# Gremar_FController.net
KiCad netlist of a schematic drawn in Altium Designer
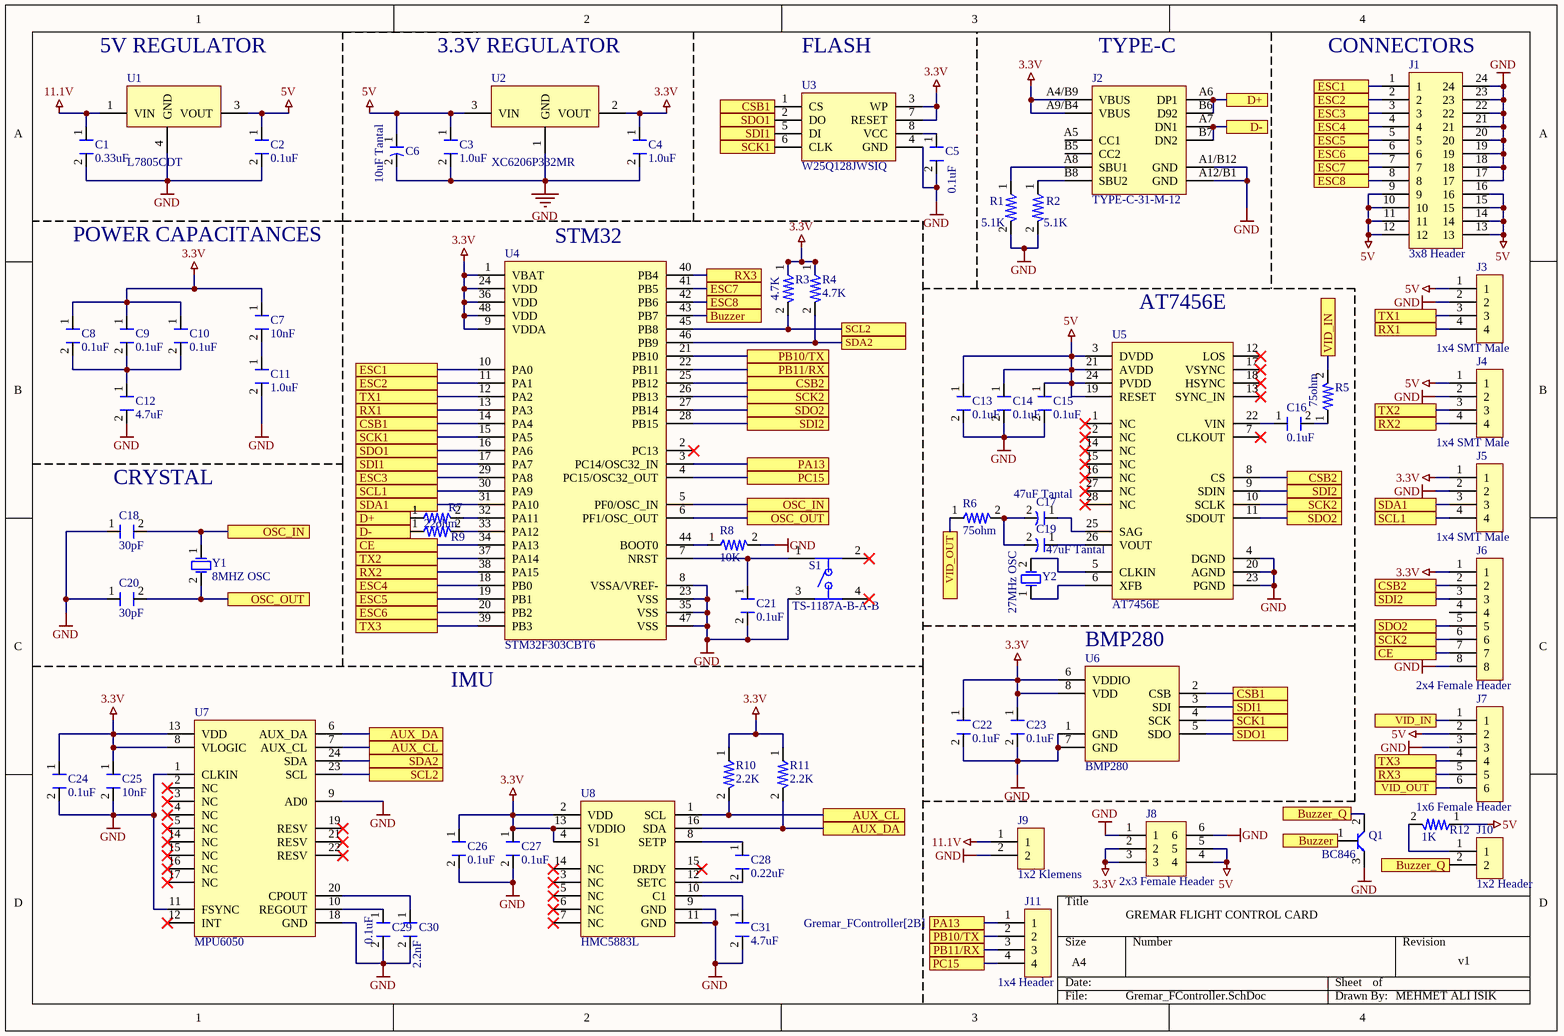
[diagram p0: Gremar_FController.SchDoc]

(export (version "E")
  (design (tool "Eeschema 10.0.6"))
  (components
    (comp (ref "C1")
      (value "0.33uF")
      (footprint "CAP - 0603")
      (description "0603 0.33uF Capacitor")
      (libsource (lib "Flight_Controller") (part "0.33uF"))
    )
    (comp (ref "C2")
      (value "0.1uF")
      (footprint "CAP - 0603")
      (description "0603 0.1uF Capacitor")
      (libsource (lib "Flight_Controller") (part "0.1uF"))
    )
    (comp (ref "C3")
      (value "1.0uF")
      (footprint "CAP - 0603")
      (description "0603 1.0uF Capacitor")
      (libsource (lib "Flight_Controller") (part "1.0uF"))
    )
    (comp (ref "C4")
      (value "1.0uF")
      (footprint "CAP - 0603")
      (description "0603 1.0uF Capacitor")
      (libsource (lib "Flight_Controller") (part "1.0uF"))
    )
    (comp (ref "C5")
      (value "0.1uF")
      (footprint "CAP - 0603")
      (description "0603 0.1uF Capacitor")
      (libsource (lib "Flight_Controller") (part "0.1uF"))
    )
    (comp (ref "C6")
      (value "10uF Tantal")
      (footprint "10uF Tantal")
      (description "10uF 16V 3Ω@100kHz -55℃~+125℃ ±10% CASE-A_3216 Tantalum Capacitors ROHS")
      (libsource (lib "Flight_Controller") (part "10uF Tantal"))
    )
    (comp (ref "C7")
      (value "10nF")
      (footprint "CAP - 0603")
      (description "0603 10nF Capacitor")
      (libsource (lib "Flight_Controller") (part "10nF"))
    )
    (comp (ref "C8")
      (value "0.1uF")
      (footprint "CAP - 0603")
      (description "0603 0.1uF Capacitor")
      (libsource (lib "Flight_Controller") (part "0.1uF"))
    )
    (comp (ref "C9")
      (value "0.1uF")
      (footprint "CAP - 0603")
      (description "0603 0.1uF Capacitor")
      (libsource (lib "Flight_Controller") (part "0.1uF"))
    )
    (comp (ref "C10")
      (value "0.1uF")
      (footprint "CAP - 0603")
      (description "0603 0.1uF Capacitor")
      (libsource (lib "Flight_Controller") (part "0.1uF"))
    )
    (comp (ref "C11")
      (value "1.0uF")
      (footprint "CAP - 0603")
      (description "0603 1.0uF Capacitor")
      (libsource (lib "Flight_Controller") (part "1.0uF"))
    )
    (comp (ref "C12")
      (value "4.7uF")
      (footprint "CAP - 0603")
      (description "0603 4.7uF Capacitor")
      (libsource (lib "Flight_Controller") (part "4.7uF"))
    )
    (comp (ref "C13")
      (value "0.1uF")
      (footprint "CAP - 0603")
      (description "0603 0.1uF Capacitor")
      (libsource (lib "Flight_Controller") (part "0.1uF"))
    )
    (comp (ref "C14")
      (value "0.1uF")
      (footprint "CAP - 0603")
      (description "0603 0.1uF Capacitor")
      (libsource (lib "Flight_Controller") (part "0.1uF"))
    )
    (comp (ref "C15")
      (value "0.1uF")
      (footprint "CAP - 0603")
      (description "0603 0.1uF Capacitor")
      (libsource (lib "Flight_Controller") (part "0.1uF"))
    )
    (comp (ref "C16")
      (value "0.1uF")
      (footprint "CAP - 0603")
      (description "0603 0.1uF Capacitor")
      (libsource (lib "Flight_Controller") (part "0.1uF"))
    )
    (comp (ref "C17")
      (value "47uF Tantal")
      (footprint "10uF Tantal")
      (description "0603 47uF Capacitor")
      (libsource (lib "Flight_Controller") (part "47uF Tantal"))
    )
    (comp (ref "C18")
      (value "30pF")
      (footprint "CAP - 0603")
      (description "0603 30pF Capacitor")
      (libsource (lib "Flight_Controller") (part "30pF"))
    )
    (comp (ref "C19")
      (value "47uF Tantal")
      (footprint "10uF Tantal")
      (description "0603 47uF Capacitor")
      (libsource (lib "Flight_Controller") (part "47uF Tantal"))
    )
    (comp (ref "C20")
      (value "30pF")
      (footprint "CAP - 0603")
      (description "0603 30pF Capacitor")
      (libsource (lib "Flight_Controller") (part "30pF"))
    )
    (comp (ref "C21")
      (value "0.1uF")
      (footprint "CAP - 0603")
      (description "0603 0.1uF Capacitor")
      (libsource (lib "Flight_Controller") (part "0.1uF"))
    )
    (comp (ref "C22")
      (value "0.1uF")
      (footprint "CAP - 0603")
      (description "0603 0.1uF Capacitor")
      (libsource (lib "Flight_Controller") (part "0.1uF"))
    )
    (comp (ref "C23")
      (value "0.1uF")
      (footprint "CAP - 0603")
      (description "0603 0.1uF Capacitor")
      (libsource (lib "Flight_Controller") (part "0.1uF"))
    )
    (comp (ref "C24")
      (value "0.1uF")
      (footprint "CAP - 0603")
      (description "0603 0.1uF Capacitor")
      (libsource (lib "Flight_Controller") (part "0.1uF"))
    )
    (comp (ref "C25")
      (value "10nF")
      (footprint "CAP - 0603")
      (description "0603 10nF Capacitor")
      (libsource (lib "Flight_Controller") (part "10nF"))
    )
    (comp (ref "C26")
      (value "0.1uF")
      (footprint "CAP - 0603")
      (description "0603 0.1uF Capacitor")
      (libsource (lib "Flight_Controller") (part "0.1uF"))
    )
    (comp (ref "C27")
      (value "0.1uF")
      (footprint "CAP - 0603")
      (description "0603 0.1uF Capacitor")
      (libsource (lib "Flight_Controller") (part "0.1uF"))
    )
    (comp (ref "C28")
      (value "0.22uF")
      (footprint "CAP - 0603")
      (description "0603 0.22uF Capacitor")
      (libsource (lib "Flight_Controller") (part "0.22uF"))
    )
    (comp (ref "C29")
      (value "0.1uF")
      (footprint "CAP - 0603")
      (description "0603 0.1uF Capacitor")
      (libsource (lib "Flight_Controller") (part "0.1uF"))
    )
    (comp (ref "C30")
      (value "2.2nF")
      (footprint "CAP - 0603")
      (description "0603 2.2nF Capacitor")
      (libsource (lib "Flight_Controller") (part "2.2nF"))
    )
    (comp (ref "C31")
      (value "4.7uF")
      (footprint "CAP - 0603")
      (description "0603 4.7uF Capacitor")
      (libsource (lib "Flight_Controller") (part "4.7uF"))
    )
    (comp (ref "J1")
      (value "3x8 Header")
      (footprint "3x8 Header")
      (description "3x8 Headear 2.54mm")
      (libsource (lib "Flight_Controller") (part "3x8 Header"))
    )
    (comp (ref "J2")
      (value "TYPE-C-31-M-12")
      (footprint "TYPE-C-31-M-12")
      (description "250mA 1 16 Female Type-C SMD USB Connectors ROHS")
      (libsource (lib "Gremar_FController") (part "TYPE-C-31-M-12"))
    )
    (comp (ref "J3")
      (value "1x4 SMT Male")
      (footprint "1x4 SMT Header")
      (description "1x4 SMT male header")
      (libsource (lib "Flight_Controller") (part "1x4 SMT Male"))
    )
    (comp (ref "J4")
      (value "1x4 SMT Male")
      (footprint "1x4 SMT Header")
      (description "1x4 SMT male header")
      (libsource (lib "Flight_Controller") (part "1x4 SMT Male"))
    )
    (comp (ref "J5")
      (value "1x4 SMT Male")
      (footprint "1x4 SMT Header")
      (description "1x4 SMT male header")
      (libsource (lib "Flight_Controller") (part "1x4 SMT Male"))
    )
    (comp (ref "J6")
      (value "2x4 Female Header")
      (footprint "2x4 Female Header")
      (description "2x4 Female Header 2.54mm")
      (libsource (lib "Flight_Controller") (part "2x4 Female Header"))
    )
    (comp (ref "J7")
      (value "1x6 Female Header")
      (footprint "1x6 FEMALE HEADER")
      (description "1x6 Female header 2.54mm")
      (libsource (lib "Gremar_FController") (part "1x6 Female Header"))
    )
    (comp (ref "J8")
      (value "2x3 Female Header")
      (footprint "2x3 Male Header")
      (description "2x3 Female header 2.54mm")
      (libsource (lib "Flight_Controller") (part "2x3 Female Header"))
    )
    (comp (ref "J9")
      (value "1x2 Klemens")
      (footprint "1x2 Klemens")
      (libsource (lib "Gremar_FController") (part "1x2 Klemens"))
    )
    (comp (ref "J10")
      (value "1x2 Header")
      (footprint "1x2 Header")
      (description "1x2 Header 2.54mm")
      (libsource (lib "Gremar_FController") (part "1x2 Header"))
    )
    (comp (ref "J11")
      (value "1x4 Header")
      (footprint "1x4 Header")
      (description "1x4 Header 2.54mm")
      (libsource (lib "Gremar_FController") (part "1x4 Header"))
    )
    (comp (ref "Q1")
      (value "BC846")
      (footprint "BC846")
      (description "SOT-23 NPN Transistor")
      (libsource (lib "Flight_Controller") (part "BC846"))
    )
    (comp (ref "R1")
      (value "5.1K")
      (footprint "RES - 0603")
      (description "0603 5.1K Resistor")
      (libsource (lib "Flight_Controller") (part "5.1K"))
    )
    (comp (ref "R2")
      (value "5.1K")
      (footprint "RES - 0603")
      (description "0603 5.1K Resistor")
      (libsource (lib "Flight_Controller") (part "5.1K"))
    )
    (comp (ref "R3")
      (value "4.7K")
      (footprint "RES - 0603")
      (description "0603 4.7K Resistor")
      (libsource (lib "Flight_Controller") (part "4.7K"))
    )
    (comp (ref "R4")
      (value "4.7K")
      (footprint "RES - 0603")
      (description "0603 4.7K Resistor")
      (libsource (lib "Flight_Controller") (part "4.7K"))
    )
    (comp (ref "R5")
      (value "75ohm")
      (footprint "RES - 0603")
      (description "0603 75ohm Resistor")
      (libsource (lib "Flight_Controller") (part "75ohm"))
    )
    (comp (ref "R6")
      (value "75ohm")
      (footprint "RES - 0603")
      (description "0603 75ohm Resistor")
      (libsource (lib "Flight_Controller") (part "75ohm"))
    )
    (comp (ref "R7")
      (value "22ohm")
      (footprint "RES - 0603")
      (description "0603 22ohm Resistor")
      (libsource (lib "Flight_Controller") (part "22ohm"))
    )
    (comp (ref "R8")
      (value "10K")
      (footprint "RES - 0603")
      (description "0603 10K Resistor")
      (libsource (lib "Flight_Controller") (part "10K"))
    )
    (comp (ref "R9")
      (value "22ohm")
      (footprint "RES - 0603")
      (description "0603 22ohm Resistor")
      (libsource (lib "Flight_Controller") (part "22ohm"))
    )
    (comp (ref "R10")
      (value "2.2K")
      (footprint "RES - 0603")
      (description "0603 2.2K Resistor")
      (libsource (lib "Flight_Controller") (part "2.2K"))
    )
    (comp (ref "R11")
      (value "2.2K")
      (footprint "RES - 0603")
      (description "0603 2.2K Resistor")
      (libsource (lib "Flight_Controller") (part "2.2K"))
    )
    (comp (ref "R12")
      (value "1K")
      (footprint "RES - 0603")
      (description "0603 1K Resistor")
      (libsource (lib "Flight_Controller") (part "1K"))
    )
    (comp (ref "S1")
      (value "TS-1187A-B-A-B")
      (footprint "TS-1187A-B-A-B")
      (libsource (lib "Flight_Controller") (part "TS-1187A-B-A-B"))
    )
    (comp (ref "U1")
      (value "L7805CDT")
      (footprint "L7805CDT-TR")
      (libsource (lib "Gremar_FController") (part "L7805CDT"))
    )
    (comp (ref "U2")
      (value "XC6206P332MR")
      (footprint "XC6206P332MR")
      (description "200mA 680mV@(100mA) Fixed 3.3V~3.3V Positive 1 6V SOT-23-3L Linear Voltage Regulators (LDO) ROHS")
      (libsource (lib "Gremar_FController") (part "XC6206P332MR"))
    )
    (comp (ref "U3")
      (value "W25Q128JWSIQ")
      (footprint "W25Q128JWSIQ")
      (description "SOIC-8_208mil NOR FLASH ROHS")
      (libsource (lib "Gremar_FController") (part "W25Q128JWSIQ"))
    )
    (comp (ref "U4")
      (value "STM32F303CBT6")
      (footprint "STM32F303CBT6")
      (description "ARM® Cortex®-M4 72MHz FLASH 2V ~ 3.6V 32-Bit LQFP-48_7x7x05P ST Microelectronics ROHS")
      (libsource (lib "Gremar_FController") (part "STM32F303CBT6"))
    )
    (comp (ref "U5")
      (value "AT7456E")
      (footprint "AT7456E")
      (description "EEPROM, TSSOP-28 Microcontroller Units (MCUs/MPUs/SOCs) ROHS")
      (libsource (lib "Gremar_FController") (part "AT7456E"))
    )
    (comp (ref "U6")
      (value "BMP280")
      (footprint "BMP280")
      (description "LGA-8 Gas Sensors ROHS")
      (libsource (lib "Gremar_FController") (part "BMP280"))
    )
    (comp (ref "U7")
      (value "MPU6050")
      (footprint "MPU-6050")
      (description "QFN-24_4x4x05P Attitude Sensors ROHSs")
      (libsource (lib "Gremar_FController") (part "MPU6050"))
    )
    (comp (ref "U8")
      (value "HMC5883L")
      (footprint "HMC5883L")
      (description "LCC-16 Magnetic Sensors ROHS")
      (libsource (lib "Gremar_FController") (part "HMC5883L"))
    )
    (comp (ref "Y1")
      (value "8MHZ OSC")
      (footprint "8MHZ RESONATOR")
      (description "8MHz ±20ppm 20pF 80Ω SMD-5032_2P SMD Crystal Resonators RoHS")
      (libsource (lib "Gremar_FController") (part "8MHZ OSC"))
    )
    (comp (ref "Y2")
      (value "27MHz OSC")
      (footprint "27MHZ OSC - 7A27000010")
      (description "27MHz ±15ppm 20pF 50Ω SMD-5032_2P SMD Crystal Resonators RoHS")
      (libsource (lib "Gremar_FController") (part "27MHz OSC"))
    )
  )
  (nets
    (net (code "1") (name "/AUX_CL") (class "Default")
      (node (ref "R10") (pin "2") (pinfunction "2_2") (pintype "passive"))
      (node (ref "U7") (pin "7") (pinfunction "AUX_CL_7") (pintype "passive"))
      (node (ref "U8") (pin "1") (pinfunction "SCL_1") (pintype "passive"))
    )
    (net (code "2") (name "/AUX_DA") (class "Default")
      (node (ref "R11") (pin "2") (pinfunction "2_2") (pintype "passive"))
      (node (ref "U7") (pin "6") (pinfunction "AUX_DA_6") (pintype "passive"))
      (node (ref "U8") (pin "16") (pinfunction "SDA_16") (pintype "passive"))
    )
    (net (code "3") (name "/Buzzer") (class "Default")
      (node (ref "Q1") (pin "1") (pinfunction "1_1") (pintype "passive"))
      (node (ref "U4") (pin "43") (pinfunction "PB7_43") (pintype "passive"))
    )
    (net (code "4") (name "/Buzzer_Q") (class "Default")
      (node (ref "J10") (pin "2") (pinfunction "2_2") (pintype "passive"))
      (node (ref "Q1") (pin "2") (pinfunction "2_2") (pintype "passive"))
    )
    (net (code "5") (name "/CE") (class "Default")
      (node (ref "J6") (pin "7") (pinfunction "7_7") (pintype "passive"))
      (node (ref "U4") (pin "34") (pinfunction "PA13_34") (pintype "passive"))
    )
    (net (code "6") (name "/CSB1") (class "Default")
      (node (ref "U3") (pin "1") (pinfunction "CS_1") (pintype "passive"))
      (node (ref "U4") (pin "14") (pinfunction "PA4_14") (pintype "passive"))
      (node (ref "U6") (pin "2") (pinfunction "CSB_2") (pintype "passive"))
    )
    (net (code "7") (name "/CSB2") (class "Default")
      (node (ref "J6") (pin "2") (pinfunction "2_2") (pintype "passive"))
      (node (ref "U4") (pin "25") (pinfunction "PB12_25") (pintype "passive"))
      (node (ref "U5") (pin "8") (pinfunction "CS_8") (pintype "passive"))
    )
    (net (code "8") (name "/D+") (class "Default")
      (node (ref "J2") (pin "A6") (pinfunction "DP1_A6") (pintype "passive"))
      (node (ref "J2") (pin "B6") (pinfunction "D92_B6") (pintype "passive"))
      (node (ref "R7") (pin "1") (pinfunction "1_1") (pintype "passive"))
    )
    (net (code "9") (name "/D-") (class "Default")
      (node (ref "J2") (pin "A7") (pinfunction "DN1_A7") (pintype "passive"))
      (node (ref "J2") (pin "B7") (pinfunction "DN2_B7") (pintype "passive"))
      (node (ref "R9") (pin "1") (pinfunction "1_1") (pintype "passive"))
    )
    (net (code "10") (name "/ESC1") (class "Default")
      (node (ref "J1") (pin "1") (pinfunction "1_1") (pintype "passive"))
      (node (ref "U4") (pin "10") (pinfunction "PA0_10") (pintype "passive"))
    )
    (net (code "11") (name "/ESC2") (class "Default")
      (node (ref "J1") (pin "2") (pinfunction "2_2") (pintype "passive"))
      (node (ref "U4") (pin "11") (pinfunction "PA1_11") (pintype "passive"))
    )
    (net (code "12") (name "/ESC3") (class "Default")
      (node (ref "J1") (pin "3") (pinfunction "3_3") (pintype "passive"))
      (node (ref "U4") (pin "29") (pinfunction "PA8_29") (pintype "passive"))
    )
    (net (code "13") (name "/ESC4") (class "Default")
      (node (ref "J1") (pin "4") (pinfunction "4_4") (pintype "passive"))
      (node (ref "U4") (pin "18") (pinfunction "PB0_18") (pintype "passive"))
    )
    (net (code "14") (name "/ESC5") (class "Default")
      (node (ref "J1") (pin "5") (pinfunction "5_5") (pintype "passive"))
      (node (ref "U4") (pin "19") (pinfunction "PB1_19") (pintype "passive"))
    )
    (net (code "15") (name "/ESC6") (class "Default")
      (node (ref "J1") (pin "6") (pinfunction "6_6") (pintype "passive"))
      (node (ref "U4") (pin "20") (pinfunction "PB2_20") (pintype "passive"))
    )
    (net (code "16") (name "/ESC7") (class "Default")
      (node (ref "J1") (pin "7") (pinfunction "7_7") (pintype "passive"))
      (node (ref "U4") (pin "41") (pinfunction "PB5_41") (pintype "passive"))
    )
    (net (code "17") (name "/ESC8") (class "Default")
      (node (ref "J1") (pin "8") (pinfunction "8_8") (pintype "passive"))
      (node (ref "U4") (pin "42") (pinfunction "PB6_42") (pintype "passive"))
    )
    (net (code "18") (name "/OSC_IN") (class "Default")
      (node (ref "C18") (pin "2") (pinfunction "2_2") (pintype "passive"))
      (node (ref "U4") (pin "5") (pinfunction "PF0/OSC_IN_5") (pintype "passive"))
      (node (ref "Y1") (pin "1") (pinfunction "1_1") (pintype "passive"))
    )
    (net (code "19") (name "/OSC_OUT") (class "Default")
      (node (ref "C20") (pin "2") (pinfunction "2_2") (pintype "passive"))
      (node (ref "U4") (pin "6") (pinfunction "PF1/OSC_OUT_6") (pintype "passive"))
      (node (ref "Y1") (pin "2") (pinfunction "2_2") (pintype "passive"))
    )
    (net (code "20") (name "/PA13") (class "Default")
      (node (ref "J11") (pin "1") (pinfunction "1_1") (pintype "passive"))
      (node (ref "U4") (pin "3") (pinfunction "PC14/OSC32_IN_3") (pintype "passive"))
    )
    (net (code "21") (name "/PB10{slash}TX") (class "Default")
      (node (ref "J11") (pin "2") (pinfunction "2_2") (pintype "passive"))
      (node (ref "U4") (pin "21") (pinfunction "PB10_21") (pintype "passive"))
    )
    (net (code "22") (name "/PB11{slash}RX") (class "Default")
      (node (ref "J11") (pin "3") (pinfunction "3_3") (pintype "passive"))
      (node (ref "U4") (pin "22") (pinfunction "PB11_22") (pintype "passive"))
    )
    (net (code "23") (name "/PC15") (class "Default")
      (node (ref "J11") (pin "4") (pinfunction "4_4") (pintype "passive"))
      (node (ref "U4") (pin "4") (pinfunction "PC15/OSC32_OUT_4") (pintype "passive"))
    )
    (net (code "24") (name "/RX1") (class "Default")
      (node (ref "J3") (pin "4") (pinfunction "4_4") (pintype "passive"))
      (node (ref "U4") (pin "13") (pinfunction "PA3_13") (pintype "passive"))
    )
    (net (code "25") (name "/RX2") (class "Default")
      (node (ref "J4") (pin "4") (pinfunction "4_4") (pintype "passive"))
      (node (ref "U4") (pin "38") (pinfunction "PA15_38") (pintype "passive"))
    )
    (net (code "26") (name "/RX3") (class "Default")
      (node (ref "J7") (pin "5") (pinfunction "5_5") (pintype "passive"))
      (node (ref "U4") (pin "40") (pinfunction "PB4_40") (pintype "passive"))
    )
    (net (code "27") (name "/SCK1") (class "Default")
      (node (ref "U3") (pin "6") (pinfunction "CLK_6") (pintype "passive"))
      (node (ref "U4") (pin "15") (pinfunction "PA5_15") (pintype "passive"))
      (node (ref "U6") (pin "4") (pinfunction "SCK_4") (pintype "passive"))
    )
    (net (code "28") (name "/SCK2") (class "Default")
      (node (ref "J6") (pin "6") (pinfunction "6_6") (pintype "passive"))
      (node (ref "U4") (pin "26") (pinfunction "PB13_26") (pintype "passive"))
      (node (ref "U5") (pin "10") (pinfunction "SCLK_10") (pintype "passive"))
    )
    (net (code "29") (name "/SCL1") (class "Default")
      (node (ref "J5") (pin "4") (pinfunction "4_4") (pintype "passive"))
      (node (ref "U4") (pin "30") (pinfunction "PA9_30") (pintype "passive"))
    )
    (net (code "30") (name "/SCL2") (class "Default")
      (node (ref "R3") (pin "2") (pinfunction "2_2") (pintype "passive"))
      (node (ref "U4") (pin "45") (pinfunction "PB8_45") (pintype "passive"))
      (node (ref "U7") (pin "23") (pinfunction "SCL_23") (pintype "passive"))
    )
    (net (code "31") (name "/SDA1") (class "Default")
      (node (ref "J5") (pin "3") (pinfunction "3_3") (pintype "passive"))
      (node (ref "U4") (pin "31") (pinfunction "PA10_31") (pintype "passive"))
    )
    (net (code "32") (name "/SDA2") (class "Default")
      (node (ref "R4") (pin "2") (pinfunction "2_2") (pintype "passive"))
      (node (ref "U4") (pin "46") (pinfunction "PB9_46") (pintype "passive"))
      (node (ref "U7") (pin "24") (pinfunction "SDA_24") (pintype "passive"))
    )
    (net (code "33") (name "/SDI1") (class "Default")
      (node (ref "U3") (pin "5") (pinfunction "DI_5") (pintype "passive"))
      (node (ref "U4") (pin "17") (pinfunction "PA7_17") (pintype "passive"))
      (node (ref "U6") (pin "3") (pinfunction "SDI_3") (pintype "passive"))
    )
    (net (code "34") (name "/SDI2") (class "Default")
      (node (ref "J6") (pin "3") (pinfunction "3_3") (pintype "passive"))
      (node (ref "U4") (pin "28") (pinfunction "PB15_28") (pintype "passive"))
      (node (ref "U5") (pin "9") (pinfunction "SDIN_9") (pintype "passive"))
    )
    (net (code "35") (name "/SDO1") (class "Default")
      (node (ref "U3") (pin "2") (pinfunction "DO_2") (pintype "passive"))
      (node (ref "U4") (pin "16") (pinfunction "PA6_16") (pintype "passive"))
      (node (ref "U6") (pin "5") (pinfunction "SDO_5") (pintype "passive"))
    )
    (net (code "36") (name "/SDO2") (class "Default")
      (node (ref "J6") (pin "5") (pinfunction "5_5") (pintype "passive"))
      (node (ref "U4") (pin "27") (pinfunction "PB14_27") (pintype "passive"))
      (node (ref "U5") (pin "11") (pinfunction "SDOUT_11") (pintype "passive"))
    )
    (net (code "37") (name "/TX1") (class "Default")
      (node (ref "J3") (pin "3") (pinfunction "3_3") (pintype "passive"))
      (node (ref "U4") (pin "12") (pinfunction "PA2_12") (pintype "passive"))
    )
    (net (code "38") (name "/TX2") (class "Default")
      (node (ref "J4") (pin "3") (pinfunction "3_3") (pintype "passive"))
      (node (ref "U4") (pin "37") (pinfunction "PA14_37") (pintype "passive"))
    )
    (net (code "39") (name "/TX3") (class "Default")
      (node (ref "J7") (pin "4") (pinfunction "4_4") (pintype "passive"))
      (node (ref "U4") (pin "39") (pinfunction "PB3_39") (pintype "passive"))
    )
    (net (code "40") (name "/VID_IN") (class "Default")
      (node (ref "J7") (pin "1") (pinfunction "1_1") (pintype "passive"))
      (node (ref "R5") (pin "2") (pinfunction "2_2") (pintype "passive"))
    )
    (net (code "41") (name "/VID_OUT") (class "Default")
      (node (ref "J7") (pin "6") (pinfunction "6_6") (pintype "passive"))
      (node (ref "R6") (pin "1") (pinfunction "1_1") (pintype "passive"))
    )
    (net (code "42") (name "3.3V") (class "Default")
      (node (ref "C10") (pin "1") (pinfunction "1_1") (pintype "passive"))
      (node (ref "C22") (pin "1") (pinfunction "1_1") (pintype "passive"))
      (node (ref "C23") (pin "1") (pinfunction "1_1") (pintype "passive"))
      (node (ref "C24") (pin "1") (pinfunction "1_1") (pintype "passive"))
      (node (ref "C25") (pin "1") (pinfunction "1_1") (pintype "passive"))
      (node (ref "C26") (pin "1") (pinfunction "1_1") (pintype "passive"))
      (node (ref "C27") (pin "1") (pinfunction "1_1") (pintype "passive"))
      (node (ref "C4") (pin "1") (pinfunction "1_1") (pintype "passive"))
      (node (ref "C7") (pin "1") (pinfunction "1_1") (pintype "passive"))
      (node (ref "C8") (pin "1") (pinfunction "1_1") (pintype "passive"))
      (node (ref "C9") (pin "1") (pinfunction "1_1") (pintype "passive"))
      (node (ref "J2") (pin "A4/B9") (pinfunction "VBUS_A4/B9") (pintype "passive"))
      (node (ref "J2") (pin "A9/B4") (pinfunction "VBUS_A9/B4") (pintype "passive"))
      (node (ref "J5") (pin "1") (pinfunction "1_1") (pintype "passive"))
      (node (ref "J6") (pin "1") (pinfunction "1_1") (pintype "passive"))
      (node (ref "J8") (pin "2") (pinfunction "2_2") (pintype "passive"))
      (node (ref "J8") (pin "3") (pinfunction "3_3") (pintype "passive"))
      (node (ref "R10") (pin "1") (pinfunction "1_1") (pintype "passive"))
      (node (ref "R11") (pin "1") (pinfunction "1_1") (pintype "passive"))
      (node (ref "R3") (pin "1") (pinfunction "1_1") (pintype "passive"))
      (node (ref "R4") (pin "1") (pinfunction "1_1") (pintype "passive"))
      (node (ref "U2") (pin "2") (pinfunction "VOUT_2") (pintype "passive"))
      (node (ref "U3") (pin "3") (pinfunction "WP_3") (pintype "passive"))
      (node (ref "U3") (pin "7") (pinfunction "RESET_7") (pintype "passive"))
      (node (ref "U4") (pin "1") (pinfunction "VBAT_1") (pintype "passive"))
      (node (ref "U4") (pin "24") (pinfunction "VDD_24") (pintype "passive"))
      (node (ref "U4") (pin "36") (pinfunction "VDD_36") (pintype "passive"))
      (node (ref "U4") (pin "48") (pinfunction "VDD_48") (pintype "passive"))
      (node (ref "U4") (pin "9") (pinfunction "VDDA_9") (pintype "passive"))
      (node (ref "U6") (pin "6") (pinfunction "VDDIO_6") (pintype "passive"))
      (node (ref "U6") (pin "8") (pinfunction "VDD_8") (pintype "passive"))
      (node (ref "U7") (pin "13") (pinfunction "VDD_13") (pintype "passive"))
      (node (ref "U7") (pin "8") (pinfunction "VLOGIC_8") (pintype "passive"))
      (node (ref "U8") (pin "13") (pinfunction "VDDIO_13") (pintype "passive"))
      (node (ref "U8") (pin "2") (pinfunction "VDD_2") (pintype "passive"))
      (node (ref "U8") (pin "4") (pinfunction "S1_4") (pintype "passive"))
    )
    (net (code "43") (name "5V") (class "Default")
      (node (ref "C13") (pin "1") (pinfunction "1_1") (pintype "passive"))
      (node (ref "C14") (pin "1") (pinfunction "1_1") (pintype "passive"))
      (node (ref "C15") (pin "1") (pinfunction "1_1") (pintype "passive"))
      (node (ref "C2") (pin "1") (pinfunction "1_1") (pintype "passive"))
      (node (ref "C3") (pin "1") (pinfunction "1_1") (pintype "passive"))
      (node (ref "C6") (pin "1") (pinfunction "1_1") (pintype "passive"))
      (node (ref "J1") (pin "10") (pinfunction "10_10") (pintype "passive"))
      (node (ref "J1") (pin "11") (pinfunction "11_11") (pintype "passive"))
      (node (ref "J1") (pin "12") (pinfunction "12_12") (pintype "passive"))
      (node (ref "J1") (pin "13") (pinfunction "13_13") (pintype "passive"))
      (node (ref "J1") (pin "14") (pinfunction "14_14") (pintype "passive"))
      (node (ref "J1") (pin "15") (pinfunction "15_15") (pintype "passive"))
      (node (ref "J1") (pin "16") (pinfunction "16_16") (pintype "passive"))
      (node (ref "J1") (pin "9") (pinfunction "9_9") (pintype "passive"))
      (node (ref "J3") (pin "1") (pinfunction "1_1") (pintype "passive"))
      (node (ref "J4") (pin "1") (pinfunction "1_1") (pintype "passive"))
      (node (ref "J7") (pin "2") (pinfunction "2_2") (pintype "passive"))
      (node (ref "J8") (pin "4") (pinfunction "4_4") (pintype "passive"))
      (node (ref "J8") (pin "5") (pinfunction "5_5") (pintype "passive"))
      (node (ref "R12") (pin "1") (pinfunction "1_1") (pintype "passive"))
      (node (ref "U1") (pin "3") (pinfunction "VOUT_3") (pintype "passive"))
      (node (ref "U2") (pin "3") (pinfunction "VIN_3") (pintype "passive"))
      (node (ref "U5") (pin "19") (pinfunction "RESET_19") (pintype "passive"))
      (node (ref "U5") (pin "21") (pinfunction "AVDD_21") (pintype "passive"))
      (node (ref "U5") (pin "24") (pinfunction "PVDD_24") (pintype "passive"))
      (node (ref "U5") (pin "3") (pinfunction "DVDD_3") (pintype "passive"))
    )
    (net (code "44") (name "11.1V") (class "Default")
      (node (ref "C1") (pin "1") (pinfunction "1_1") (pintype "passive"))
      (node (ref "J9") (pin "1") (pinfunction "1_1") (pintype "passive"))
      (node (ref "U1") (pin "1") (pinfunction "VIN_1") (pintype "passive"))
    )
    (net (code "45") (name "GND") (class "Default")
      (node (ref "C1") (pin "2") (pinfunction "2_2") (pintype "passive"))
      (node (ref "C11") (pin "2") (pinfunction "2_2") (pintype "passive"))
      (node (ref "C12") (pin "2") (pinfunction "2_2") (pintype "passive"))
      (node (ref "C13") (pin "2") (pinfunction "2_2") (pintype "passive"))
      (node (ref "C14") (pin "2") (pinfunction "2_2") (pintype "passive"))
      (node (ref "C15") (pin "2") (pinfunction "2_2") (pintype "passive"))
      (node (ref "C18") (pin "1") (pinfunction "1_1") (pintype "passive"))
      (node (ref "C2") (pin "2") (pinfunction "2_2") (pintype "passive"))
      (node (ref "C20") (pin "1") (pinfunction "1_1") (pintype "passive"))
      (node (ref "C21") (pin "2") (pinfunction "2_2") (pintype "passive"))
      (node (ref "C22") (pin "2") (pinfunction "2_2") (pintype "passive"))
      (node (ref "C23") (pin "2") (pinfunction "2_2") (pintype "passive"))
      (node (ref "C24") (pin "2") (pinfunction "2_2") (pintype "passive"))
      (node (ref "C25") (pin "2") (pinfunction "2_2") (pintype "passive"))
      (node (ref "C26") (pin "2") (pinfunction "2_2") (pintype "passive"))
      (node (ref "C27") (pin "2") (pinfunction "2_2") (pintype "passive"))
      (node (ref "C29") (pin "2") (pinfunction "2_2") (pintype "passive"))
      (node (ref "C3") (pin "2") (pinfunction "2_2") (pintype "passive"))
      (node (ref "C30") (pin "2") (pinfunction "2_2") (pintype "passive"))
      (node (ref "C31") (pin "2") (pinfunction "2_2") (pintype "passive"))
      (node (ref "C4") (pin "2") (pinfunction "2_2") (pintype "passive"))
      (node (ref "C5") (pin "2") (pinfunction "2_2") (pintype "passive"))
      (node (ref "C6") (pin "2") (pinfunction "2_2") (pintype "passive"))
      (node (ref "J1") (pin "17") (pinfunction "17_17") (pintype "passive"))
      (node (ref "J1") (pin "18") (pinfunction "18_18") (pintype "passive"))
      (node (ref "J1") (pin "19") (pinfunction "19_19") (pintype "passive"))
      (node (ref "J1") (pin "20") (pinfunction "20_20") (pintype "passive"))
      (node (ref "J1") (pin "21") (pinfunction "21_21") (pintype "passive"))
      (node (ref "J1") (pin "22") (pinfunction "22_22") (pintype "passive"))
      (node (ref "J1") (pin "23") (pinfunction "23_23") (pintype "passive"))
      (node (ref "J1") (pin "24") (pinfunction "24_24") (pintype "passive"))
      (node (ref "J2") (pin "A1/B12") (pinfunction "GND_A1/B12") (pintype "passive"))
      (node (ref "J2") (pin "A12/B1") (pinfunction "GND_A12/B1") (pintype "passive"))
      (node (ref "J3") (pin "2") (pinfunction "2_2") (pintype "passive"))
      (node (ref "J4") (pin "2") (pinfunction "2_2") (pintype "passive"))
      (node (ref "J5") (pin "2") (pinfunction "2_2") (pintype "passive"))
      (node (ref "J6") (pin "8") (pinfunction "8_8") (pintype "passive"))
      (node (ref "J7") (pin "3") (pinfunction "3_3") (pintype "passive"))
      (node (ref "J8") (pin "1") (pinfunction "1_1") (pintype "passive"))
      (node (ref "J8") (pin "6") (pinfunction "6_6") (pintype "passive"))
      (node (ref "J9") (pin "2") (pinfunction "2_2") (pintype "passive"))
      (node (ref "Q1") (pin "3") (pinfunction "3_3") (pintype "passive"))
      (node (ref "R1") (pin "2") (pinfunction "2_2") (pintype "passive"))
      (node (ref "R2") (pin "2") (pinfunction "2_2") (pintype "passive"))
      (node (ref "R8") (pin "2") (pinfunction "2_2") (pintype "passive"))
      (node (ref "S1") (pin "3") (pinfunction "3_3") (pintype "passive"))
      (node (ref "U1") (pin "4") (pinfunction "GND_4") (pintype "passive"))
      (node (ref "U2") (pin "1") (pinfunction "GND_1") (pintype "passive"))
      (node (ref "U3") (pin "4") (pinfunction "GND_4") (pintype "passive"))
      (node (ref "U4") (pin "23") (pinfunction "VSS_23") (pintype "passive"))
      (node (ref "U4") (pin "35") (pinfunction "VSS_35") (pintype "passive"))
      (node (ref "U4") (pin "47") (pinfunction "VSS_47") (pintype "passive"))
      (node (ref "U4") (pin "8") (pinfunction "VSSA/VREF-_8") (pintype "passive"))
      (node (ref "U5") (pin "20") (pinfunction "AGND_20") (pintype "passive"))
      (node (ref "U5") (pin "23") (pinfunction "PGND_23") (pintype "passive"))
      (node (ref "U5") (pin "4") (pinfunction "DGND_4") (pintype "passive"))
      (node (ref "U6") (pin "1") (pinfunction "GND_1") (pintype "passive"))
      (node (ref "U6") (pin "7") (pinfunction "GND_7") (pintype "passive"))
      (node (ref "U7") (pin "1") (pinfunction "CLKIN_1") (pintype "passive"))
      (node (ref "U7") (pin "11") (pinfunction "FSYNC_11") (pintype "passive"))
      (node (ref "U7") (pin "18") (pinfunction "GND_18") (pintype "passive"))
      (node (ref "U7") (pin "9") (pinfunction "AD0_9") (pintype "passive"))
      (node (ref "U8") (pin "11") (pinfunction "GND_11") (pintype "passive"))
      (node (ref "U8") (pin "9") (pinfunction "GND_9") (pintype "passive"))
    )
    (net (code "46") (name "Net-(C10-Pad2)") (class "Default")
      (node (ref "C10") (pin "2") (pinfunction "2_2") (pintype "passive"))
      (node (ref "C12") (pin "1") (pinfunction "1_1") (pintype "passive"))
      (node (ref "C8") (pin "2") (pinfunction "2_2") (pintype "passive"))
      (node (ref "C9") (pin "2") (pinfunction "2_2") (pintype "passive"))
    )
    (net (code "47") (name "Net-(C11-Pad1)") (class "Default")
      (node (ref "C11") (pin "1") (pinfunction "1_1") (pintype "passive"))
      (node (ref "C7") (pin "2") (pinfunction "2_2") (pintype "passive"))
    )
    (net (code "48") (name "Net-(C16-Pad2)") (class "Default")
      (node (ref "C16") (pin "2") (pinfunction "2_2") (pintype "passive"))
      (node (ref "R5") (pin "1") (pinfunction "1_1") (pintype "passive"))
    )
    (net (code "49") (name "Net-(C17-Pad2)") (class "Default")
      (node (ref "C17") (pin "2") (pinfunction "2_2") (pintype "passive"))
      (node (ref "C19") (pin "2") (pinfunction "2_2") (pintype "passive"))
      (node (ref "R6") (pin "2") (pinfunction "2_2") (pintype "passive"))
    )
    (net (code "50") (name "Net-(J2-SBU1)") (class "Default")
      (node (ref "J2") (pin "A8") (pinfunction "SBU1_A8") (pintype "passive"))
      (node (ref "R1") (pin "1") (pinfunction "1_1") (pintype "passive"))
    )
    (net (code "51") (name "Net-(J2-SBU2)") (class "Default")
      (node (ref "J2") (pin "B8") (pinfunction "SBU2_B8") (pintype "passive"))
      (node (ref "R2") (pin "1") (pinfunction "1_1") (pintype "passive"))
    )
    (net (code "52") (name "Net-(J10-Pad1)") (class "Default")
      (node (ref "J10") (pin "1") (pinfunction "1_1") (pintype "passive"))
      (node (ref "R12") (pin "2") (pinfunction "2_2") (pintype "passive"))
    )
    (net (code "53") (name "Net-(U3-VCC)") (class "Default")
      (node (ref "C5") (pin "1") (pinfunction "1_1") (pintype "passive"))
      (node (ref "U3") (pin "8") (pinfunction "VCC_8") (pintype "passive"))
    )
    (net (code "54") (name "Net-(U4-BOOT0)") (class "Default")
      (node (ref "R8") (pin "1") (pinfunction "1_1") (pintype "passive"))
      (node (ref "U4") (pin "44") (pinfunction "BOOT0_44") (pintype "passive"))
    )
    (net (code "55") (name "Net-(U4-NRST)") (class "Default")
      (node (ref "C21") (pin "1") (pinfunction "1_1") (pintype "passive"))
      (node (ref "S1") (pin "1") (pinfunction "1_1") (pintype "passive"))
      (node (ref "U4") (pin "7") (pinfunction "NRST_7") (pintype "passive"))
    )
    (net (code "56") (name "Net-(U4-PA11)") (class "Default")
      (node (ref "R7") (pin "2") (pinfunction "2_2") (pintype "passive"))
      (node (ref "U4") (pin "32") (pinfunction "PA11_32") (pintype "passive"))
    )
    (net (code "57") (name "Net-(U4-PA12)") (class "Default")
      (node (ref "R9") (pin "2") (pinfunction "2_2") (pintype "passive"))
      (node (ref "U4") (pin "33") (pinfunction "PA12_33") (pintype "passive"))
    )
    (net (code "58") (name "Net-(U5-CLKIN)") (class "Default")
      (node (ref "U5") (pin "5") (pinfunction "CLKIN_5") (pintype "passive"))
      (node (ref "Y2") (pin "2") (pinfunction "2_2") (pintype "passive"))
    )
    (net (code "59") (name "Net-(U5-SAG)") (class "Default")
      (node (ref "C17") (pin "1") (pinfunction "1_1") (pintype "passive"))
      (node (ref "U5") (pin "25") (pinfunction "SAG_25") (pintype "passive"))
    )
    (net (code "60") (name "Net-(U5-VIN)") (class "Default")
      (node (ref "C16") (pin "1") (pinfunction "1_1") (pintype "passive"))
      (node (ref "U5") (pin "22") (pinfunction "VIN_22") (pintype "passive"))
    )
    (net (code "61") (name "Net-(U5-VOUT)") (class "Default")
      (node (ref "C19") (pin "1") (pinfunction "1_1") (pintype "passive"))
      (node (ref "U5") (pin "26") (pinfunction "VOUT_26") (pintype "passive"))
    )
    (net (code "62") (name "Net-(U5-XFB)") (class "Default")
      (node (ref "U5") (pin "6") (pinfunction "XFB_6") (pintype "passive"))
      (node (ref "Y2") (pin "1") (pinfunction "1_1") (pintype "passive"))
    )
    (net (code "63") (name "Net-(U7-CPOUT)") (class "Default")
      (node (ref "C30") (pin "1") (pinfunction "1_1") (pintype "passive"))
      (node (ref "U7") (pin "20") (pinfunction "CPOUT_20") (pintype "passive"))
    )
    (net (code "64") (name "Net-(U7-REGOUT)") (class "Default")
      (node (ref "C29") (pin "1") (pinfunction "1_1") (pintype "passive"))
      (node (ref "U7") (pin "10") (pinfunction "REGOUT_10") (pintype "passive"))
    )
    (net (code "65") (name "Net-(U8-C1)") (class "Default")
      (node (ref "C31") (pin "1") (pinfunction "1_1") (pintype "passive"))
      (node (ref "U8") (pin "10") (pinfunction "C1_10") (pintype "passive"))
    )
    (net (code "66") (name "Net-(U8-SETC)") (class "Default")
      (node (ref "C28") (pin "2") (pinfunction "2_2") (pintype "passive"))
      (node (ref "U8") (pin "12") (pinfunction "SETC_12") (pintype "passive"))
    )
    (net (code "67") (name "Net-(U8-SETP)") (class "Default")
      (node (ref "C28") (pin "1") (pinfunction "1_1") (pintype "passive"))
      (node (ref "U8") (pin "8") (pinfunction "SETP_8") (pintype "passive"))
    )
    (net (code "68") (name "unconnected-(J2-CC1-PadA5)") (class "Default")
      (node (ref "J2") (pin "A5") (pinfunction "CC1_A5") (pintype "passive"))
    )
    (net (code "69") (name "unconnected-(J2-CC2-PadB5)") (class "Default")
      (node (ref "J2") (pin "B5") (pinfunction "CC2_B5") (pintype "passive"))
    )
    (net (code "70") (name "unconnected-(J6-Pad4)") (class "Default")
      (node (ref "J6") (pin "4") (pinfunction "4_4") (pintype "passive"))
    )
    (net (code "71") (name "unconnected-(S1-Pad2)") (class "Default")
      (node (ref "S1") (pin "2") (pinfunction "2_2") (pintype "passive+no_connect"))
    )
    (net (code "72") (name "unconnected-(S1-Pad4)") (class "Default")
      (node (ref "S1") (pin "4") (pinfunction "4_4") (pintype "passive+no_connect"))
    )
    (net (code "73") (name "unconnected-(U4-PC13-Pad2)") (class "Default")
      (node (ref "U4") (pin "2") (pinfunction "PC13_2") (pintype "passive+no_connect"))
    )
    (net (code "74") (name "unconnected-(U5-CLKOUT-Pad7)") (class "Default")
      (node (ref "U5") (pin "7") (pinfunction "CLKOUT_7") (pintype "passive+no_connect"))
    )
    (net (code "75") (name "unconnected-(U5-HSYNC-Pad18)") (class "Default")
      (node (ref "U5") (pin "18") (pinfunction "HSYNC_18") (pintype "passive+no_connect"))
    )
    (net (code "76") (name "unconnected-(U5-LOS-Pad12)") (class "Default")
      (node (ref "U5") (pin "12") (pinfunction "LOS_12") (pintype "passive+no_connect"))
    )
    (net (code "77") (name "unconnected-(U5-NC-Pad1)") (class "Default")
      (node (ref "U5") (pin "1") (pinfunction "NC_1") (pintype "passive+no_connect"))
    )
    (net (code "78") (name "unconnected-(U5-NC-Pad2)") (class "Default")
      (node (ref "U5") (pin "2") (pinfunction "NC_2") (pintype "passive+no_connect"))
    )
    (net (code "79") (name "unconnected-(U5-NC-Pad14)") (class "Default")
      (node (ref "U5") (pin "14") (pinfunction "NC_14") (pintype "passive+no_connect"))
    )
    (net (code "80") (name "unconnected-(U5-NC-Pad15)") (class "Default")
      (node (ref "U5") (pin "15") (pinfunction "NC_15") (pintype "passive+no_connect"))
    )
    (net (code "81") (name "unconnected-(U5-NC-Pad16)") (class "Default")
      (node (ref "U5") (pin "16") (pinfunction "NC_16") (pintype "passive+no_connect"))
    )
    (net (code "82") (name "unconnected-(U5-NC-Pad27)") (class "Default")
      (node (ref "U5") (pin "27") (pinfunction "NC_27") (pintype "passive+no_connect"))
    )
    (net (code "83") (name "unconnected-(U5-NC-Pad28)") (class "Default")
      (node (ref "U5") (pin "28") (pinfunction "NC_28") (pintype "passive+no_connect"))
    )
    (net (code "84") (name "unconnected-(U5-SYNC_IN-Pad13)") (class "Default")
      (node (ref "U5") (pin "13") (pinfunction "SYNC_IN_13") (pintype "passive+no_connect"))
    )
    (net (code "85") (name "unconnected-(U5-VSYNC-Pad17)") (class "Default")
      (node (ref "U5") (pin "17") (pinfunction "VSYNC_17") (pintype "passive+no_connect"))
    )
    (net (code "86") (name "unconnected-(U7-INT-Pad12)") (class "Default")
      (node (ref "U7") (pin "12") (pinfunction "INT_12") (pintype "passive+no_connect"))
    )
    (net (code "87") (name "unconnected-(U7-NC-Pad2)") (class "Default")
      (node (ref "U7") (pin "2") (pinfunction "NC_2") (pintype "passive+no_connect"))
    )
    (net (code "88") (name "unconnected-(U7-NC-Pad3)") (class "Default")
      (node (ref "U7") (pin "3") (pinfunction "NC_3") (pintype "passive+no_connect"))
    )
    (net (code "89") (name "unconnected-(U7-NC-Pad4)") (class "Default")
      (node (ref "U7") (pin "4") (pinfunction "NC_4") (pintype "passive+no_connect"))
    )
    (net (code "90") (name "unconnected-(U7-NC-Pad5)") (class "Default")
      (node (ref "U7") (pin "5") (pinfunction "NC_5") (pintype "passive+no_connect"))
    )
    (net (code "91") (name "unconnected-(U7-NC-Pad14)") (class "Default")
      (node (ref "U7") (pin "14") (pinfunction "NC_14") (pintype "passive+no_connect"))
    )
    (net (code "92") (name "unconnected-(U7-NC-Pad15)") (class "Default")
      (node (ref "U7") (pin "15") (pinfunction "NC_15") (pintype "passive+no_connect"))
    )
    (net (code "93") (name "unconnected-(U7-NC-Pad16)") (class "Default")
      (node (ref "U7") (pin "16") (pinfunction "NC_16") (pintype "passive+no_connect"))
    )
    (net (code "94") (name "unconnected-(U7-NC-Pad17)") (class "Default")
      (node (ref "U7") (pin "17") (pinfunction "NC_17") (pintype "passive+no_connect"))
    )
    (net (code "95") (name "unconnected-(U7-RESV-Pad19)") (class "Default")
      (node (ref "U7") (pin "19") (pinfunction "RESV_19") (pintype "passive+no_connect"))
    )
    (net (code "96") (name "unconnected-(U7-RESV-Pad21)") (class "Default")
      (node (ref "U7") (pin "21") (pinfunction "RESV_21") (pintype "passive+no_connect"))
    )
    (net (code "97") (name "unconnected-(U7-RESV-Pad22)") (class "Default")
      (node (ref "U7") (pin "22") (pinfunction "RESV_22") (pintype "passive+no_connect"))
    )
    (net (code "98") (name "unconnected-(U8-DRDY-Pad15)") (class "Default")
      (node (ref "U8") (pin "15") (pinfunction "DRDY_15") (pintype "passive+no_connect"))
    )
    (net (code "99") (name "unconnected-(U8-NC-Pad3)") (class "Default")
      (node (ref "U8") (pin "3") (pinfunction "NC_3") (pintype "passive+no_connect"))
    )
    (net (code "100") (name "unconnected-(U8-NC-Pad5)") (class "Default")
      (node (ref "U8") (pin "5") (pinfunction "NC_5") (pintype "passive+no_connect"))
    )
    (net (code "101") (name "unconnected-(U8-NC-Pad6)") (class "Default")
      (node (ref "U8") (pin "6") (pinfunction "NC_6") (pintype "passive+no_connect"))
    )
    (net (code "102") (name "unconnected-(U8-NC-Pad7)") (class "Default")
      (node (ref "U8") (pin "7") (pinfunction "NC_7") (pintype "passive+no_connect"))
    )
    (net (code "103") (name "unconnected-(U8-NC-Pad14)") (class "Default")
      (node (ref "U8") (pin "14") (pinfunction "NC_14") (pintype "passive+no_connect"))
    )
  )
)
